# OrmerodController.net
KiCad netlist of a schematic drawn in EAGLE
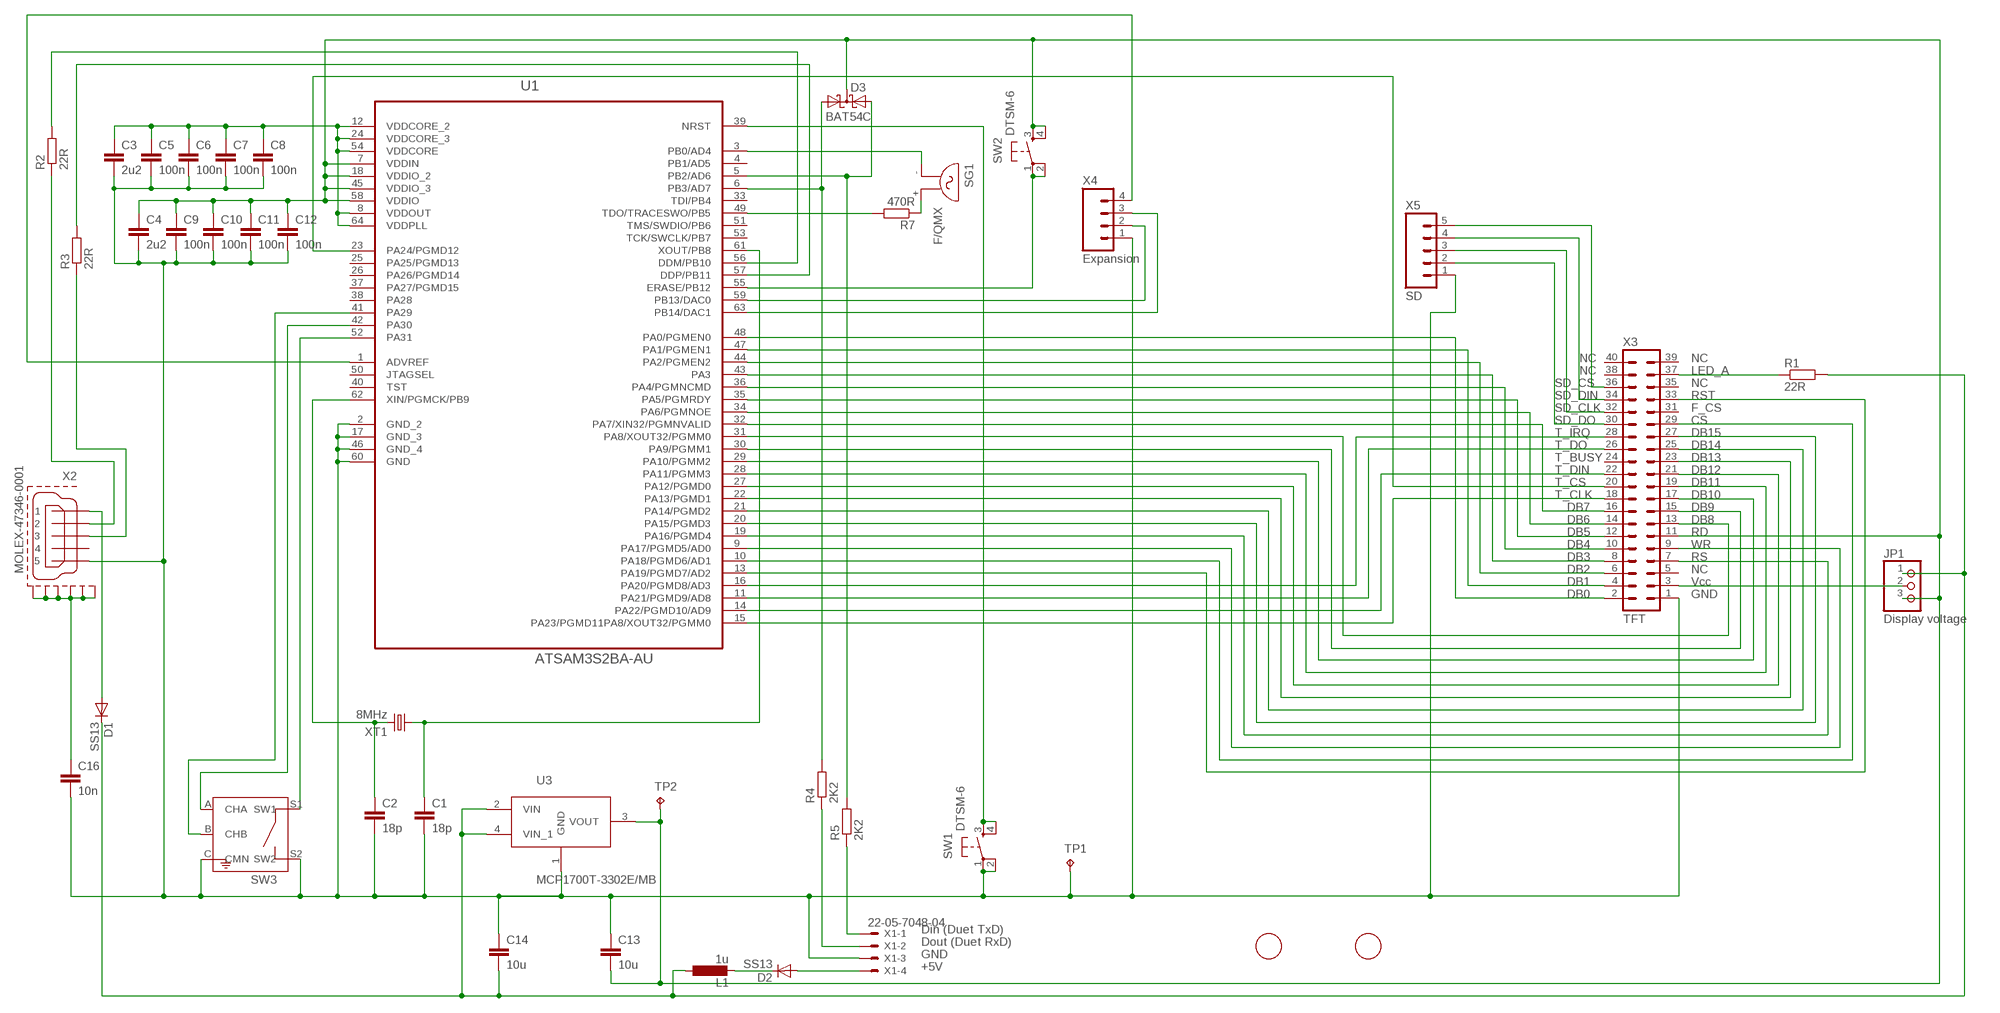
[diagram p0: schematic, sheet 1]

(export (version "E")
  (design (tool "Eeschema 10.0.6"))
  (components
    (comp (ref "C1")
      (value "18p")
      (footprint "eagle-import:C0603")
      (libsource (lib "eagle-import") (part "C-EUC0603"))
    )
    (comp (ref "C2")
      (value "18p")
      (footprint "eagle-import:C0603")
      (libsource (lib "eagle-import") (part "C-EUC0603"))
    )
    (comp (ref "C3")
      (value "2u2")
      (footprint "eagle-import:C0603")
      (libsource (lib "eagle-import") (part "C-EUC0603"))
    )
    (comp (ref "C4")
      (value "2u2")
      (footprint "eagle-import:C0603")
      (libsource (lib "eagle-import") (part "C-EUC0603"))
    )
    (comp (ref "C5")
      (value "100n")
      (footprint "eagle-import:C0603")
      (libsource (lib "eagle-import") (part "C-EUC0603"))
    )
    (comp (ref "C6")
      (value "100n")
      (footprint "eagle-import:C0603")
      (libsource (lib "eagle-import") (part "C-EUC0603"))
    )
    (comp (ref "C7")
      (value "100n")
      (footprint "eagle-import:C0603")
      (libsource (lib "eagle-import") (part "C-EUC0603"))
    )
    (comp (ref "C8")
      (value "100n")
      (footprint "eagle-import:C0603")
      (libsource (lib "eagle-import") (part "C-EUC0603"))
    )
    (comp (ref "C9")
      (value "100n")
      (footprint "eagle-import:C0603")
      (libsource (lib "eagle-import") (part "C-EUC0603"))
    )
    (comp (ref "C10")
      (value "100n")
      (footprint "eagle-import:C0603")
      (libsource (lib "eagle-import") (part "C-EUC0603"))
    )
    (comp (ref "C11")
      (value "100n")
      (footprint "eagle-import:C0603")
      (libsource (lib "eagle-import") (part "C-EUC0603"))
    )
    (comp (ref "C12")
      (value "100n")
      (footprint "eagle-import:C0603")
      (libsource (lib "eagle-import") (part "C-EUC0603"))
    )
    (comp (ref "C13")
      (value "10u")
      (footprint "eagle-import:C0805")
      (libsource (lib "eagle-import") (part "C-EUC0805"))
    )
    (comp (ref "C14")
      (value "10u")
      (footprint "eagle-import:C0805")
      (libsource (lib "eagle-import") (part "C-EUC0805"))
    )
    (comp (ref "C16")
      (value "10n")
      (footprint "eagle-import:C0603")
      (libsource (lib "eagle-import") (part "C-EUC0603"))
    )
    (comp (ref "D1")
      (value "SS13")
      (footprint "eagle-import:DO214AC")
      (libsource (lib "eagle-import") (part "DIODE-DO214AC"))
    )
    (comp (ref "D2")
      (value "SS13")
      (footprint "eagle-import:DO214AC")
      (libsource (lib "eagle-import") (part "DIODE-DO214AC"))
    )
    (comp (ref "D3")
      (value "BAT54C")
      (footprint "eagle-import:SOT23")
      (libsource (lib "eagle-import") (part "BAT54C"))
    )
    (comp (ref "JP1")
      (value "Display voltage")
      (footprint "eagle-import:1X03")
      (libsource (lib "eagle-import") (part "PINHD-1X3"))
    )
    (comp (ref "L1")
      (value "1u")
      (footprint "eagle-import:L2012C")
      (libsource (lib "eagle-import") (part "L-EUL2012C"))
    )
    (comp (ref "R1")
      (value "22R")
      (footprint "eagle-import:R0805")
      (libsource (lib "eagle-import") (part "R-EU_R0805"))
    )
    (comp (ref "R2")
      (value "22R")
      (footprint "eagle-import:R0603")
      (libsource (lib "eagle-import") (part "R-EU_R0603"))
    )
    (comp (ref "R3")
      (value "22R")
      (footprint "eagle-import:R0603")
      (libsource (lib "eagle-import") (part "R-EU_R0603"))
    )
    (comp (ref "R4")
      (value "2K2")
      (footprint "eagle-import:R0603")
      (libsource (lib "eagle-import") (part "R-EU_R0603"))
    )
    (comp (ref "R5")
      (value "2K2")
      (footprint "eagle-import:R0603")
      (libsource (lib "eagle-import") (part "R-EU_R0603"))
    )
    (comp (ref "R7")
      (value "470R")
      (footprint "eagle-import:R0603")
      (libsource (lib "eagle-import") (part "R-EU_R0603"))
    )
    (comp (ref "SG1")
      (value "F/QMX")
      (footprint "eagle-import:F_QMX")
      (libsource (lib "eagle-import") (part "F/QMX"))
    )
    (comp (ref "SW1")
      (value "DTSM-6")
      (footprint "eagle-import:DTSM-6")
      (libsource (lib "eagle-import") (part "DTSM-6"))
    )
    (comp (ref "SW2")
      (value "DTSM-6")
      (footprint "eagle-import:DTSM-6")
      (libsource (lib "eagle-import") (part "DTSM-6"))
    )
    (comp (ref "SW3")
      (value "PEC12_ENCODER")
      (footprint "eagle-import:PEC12_ENCODER")
      (libsource (lib "eagle-import") (part "PEC12_ENCODER"))
    )
    (comp (ref "TP1")
      (value "TPPAD1-10")
      (footprint "eagle-import:P1-10")
      (libsource (lib "eagle-import") (part "TPPAD1-10"))
    )
    (comp (ref "TP2")
      (value "TPPAD1-10")
      (footprint "eagle-import:P1-10")
      (libsource (lib "eagle-import") (part "TPPAD1-10"))
    )
    (comp (ref "U$1")
      (value "FIDUCIAL")
      (footprint "eagle-import:FIDUCIAL_1MM")
      (libsource (lib "eagle-import") (part "FIDUCIAL"))
    )
    (comp (ref "U$2")
      (value "FIDUCIAL")
      (footprint "eagle-import:FIDUCIAL_1MM")
      (libsource (lib "eagle-import") (part "FIDUCIAL"))
    )
    (comp (ref "U1")
      (value "ATSAM3S2BA-AU")
      (footprint "eagle-import:QFP50P1200X1200X160-64N")
      (libsource (lib "eagle-import") (part "ATSAM3S2BA-AU"))
    )
    (comp (ref "U3")
      (value "MCP1700T-3302E/MB")
      (footprint "eagle-import:SOT150P400X160-4N")
      (fields (field (name "MPN") "MCP1702T-3302E/MB"))
      (libsource (lib "eagle-import") (part "MCP17-MCP1702T-3302E/MB"))
    )
    (comp (ref "X1")
      (value "22-05-7048-04")
      (footprint "eagle-import:7395-04")
      (libsource (lib "eagle-import") (part "22-?-0405-7048"))
    )
    (comp (ref "X2")
      (value "MOLEX-47346-0001")
      (footprint "eagle-import:MOLEX-47364-0001")
      (libsource (lib "eagle-import") (part "MOLEX-47346-0001"))
    )
    (comp (ref "X3")
      (value "TFT")
      (footprint "eagle-import:MA20-2")
      (libsource (lib "eagle-import") (part "MA20-2"))
    )
    (comp (ref "X4")
      (value "Expansion")
      (footprint "eagle-import:1X04")
      (libsource (lib "eagle-import") (part "M04PTH"))
    )
    (comp (ref "X5")
      (value "SD")
      (footprint "eagle-import:1X05")
      (libsource (lib "eagle-import") (part "M05PTH"))
    )
    (comp (ref "XT1")
      (value "8MHz")
      (footprint "eagle-import:HC49U-V")
      (libsource (lib "eagle-import") (part "CRYSTALHC49U-V"))
    )
  )
  (nets
    (net (code "1") (name "Net-(C16-Pad1)") (class "Default")
      (node (ref "C16") (pin "1") (pinfunction "1_1") (pintype "passive"))
      (node (ref "X2") (pin "GND1") (pinfunction "GND1_GND1") (pintype "bidirectional"))
      (node (ref "X2") (pin "GND2") (pinfunction "GND2_GND2") (pintype "bidirectional"))
      (node (ref "X2") (pin "GND3") (pinfunction "GND3_GND3") (pintype "bidirectional"))
      (node (ref "X2") (pin "GND4") (pinfunction "GND4_GND4") (pintype "bidirectional"))
      (node (ref "X2") (pin "GND5") (pinfunction "GND5_GND5") (pintype "bidirectional"))
      (node (ref "X2") (pin "GND6") (pinfunction "GND6_GND6") (pintype "bidirectional"))
    )
    (net (code "2") (name "Net-(D1-PadA)") (class "Default")
      (node (ref "D1") (pin "A") (pinfunction "A_A") (pintype "passive"))
      (node (ref "X2") (pin "1") (pinfunction "1_1") (pintype "input"))
    )
    (net (code "3") (name "Net-(D2-PadC)") (class "Default")
      (node (ref "D2") (pin "C") (pinfunction "C_C") (pintype "passive"))
      (node (ref "L1") (pin "2") (pinfunction "2_2") (pintype "passive"))
    )
    (net (code "4") (name "Net-(D3-A1)") (class "Default")
      (node (ref "D3") (pin "1") (pinfunction "A1_1") (pintype "passive"))
      (node (ref "R4") (pin "2") (pinfunction "2_2") (pintype "passive"))
      (node (ref "U1") (pin "6") (pinfunction "PB3/AD7_6") (pintype "bidirectional"))
    )
    (net (code "5") (name "Net-(D3-A2)") (class "Default")
      (node (ref "D3") (pin "2") (pinfunction "A2_2") (pintype "passive"))
      (node (ref "R5") (pin "2") (pinfunction "2_2") (pintype "passive"))
      (node (ref "U1") (pin "5") (pinfunction "PB2/AD6_5") (pintype "bidirectional"))
    )
    (net (code "6") (name "Net-(D3-CC)") (class "Default")
      (node (ref "C10") (pin "1") (pinfunction "1_1") (pintype "passive"))
      (node (ref "C11") (pin "1") (pinfunction "1_1") (pintype "passive"))
      (node (ref "C12") (pin "1") (pinfunction "1_1") (pintype "passive"))
      (node (ref "C13") (pin "2") (pinfunction "2_2") (pintype "passive"))
      (node (ref "C4") (pin "1") (pinfunction "1_1") (pintype "passive"))
      (node (ref "C9") (pin "1") (pinfunction "1_1") (pintype "passive"))
      (node (ref "D3") (pin "3") (pinfunction "CC_3") (pintype "passive"))
      (node (ref "JP1") (pin "3") (pinfunction "3_3") (pintype "passive"))
      (node (ref "SW2") (pin "3") (pinfunction "3_3") (pintype "passive"))
      (node (ref "SW2") (pin "4") (pinfunction "4_4") (pintype "passive"))
      (node (ref "TP2") (pin "TP") (pinfunction "TP_TP") (pintype "input"))
      (node (ref "U1") (pin "18") (pinfunction "VDDIO_2_18") (pintype "power_in"))
      (node (ref "U1") (pin "45") (pinfunction "VDDIO_3_45") (pintype "power_in"))
      (node (ref "U1") (pin "58") (pinfunction "VDDIO_58") (pintype "power_in"))
      (node (ref "U1") (pin "7") (pinfunction "VDDIN_7") (pintype "power_in"))
      (node (ref "U3") (pin "3") (pinfunction "VOUT_3") (pintype "output"))
      (node (ref "X3") (pin "11") (pinfunction "11_11") (pintype "passive"))
    )
    (net (code "7") (name "Net-(JP1-Pad2)") (class "Default")
      (node (ref "JP1") (pin "2") (pinfunction "2_2") (pintype "passive"))
      (node (ref "X3") (pin "3") (pinfunction "3_3") (pintype "passive"))
    )
    (net (code "8") (name "Net-(R1-Pad1)") (class "Default")
      (node (ref "R1") (pin "1") (pinfunction "1_1") (pintype "passive"))
      (node (ref "X3") (pin "37") (pinfunction "37_37") (pintype "passive"))
    )
    (net (code "9") (name "Net-(R2-Pad1)") (class "Default")
      (node (ref "R2") (pin "1") (pinfunction "1_1") (pintype "passive"))
      (node (ref "X2") (pin "2") (pinfunction "2_2") (pintype "input"))
    )
    (net (code "10") (name "Net-(R3-Pad1)") (class "Default")
      (node (ref "R3") (pin "1") (pinfunction "1_1") (pintype "passive"))
      (node (ref "X2") (pin "3") (pinfunction "3_3") (pintype "input"))
    )
    (net (code "11") (name "Net-(SG1-1)") (class "Default")
      (node (ref "SG1") (pin "-") (pinfunction "1_-") (pintype "passive"))
      (node (ref "U1") (pin "3") (pinfunction "PB0/AD4_3") (pintype "bidirectional"))
    )
    (net (code "12") (name "Net-(SG1-2)") (class "Default")
      (node (ref "R7") (pin "1") (pinfunction "1_1") (pintype "passive"))
      (node (ref "SG1") (pin "+") (pinfunction "2_+") (pintype "passive"))
    )
    (net (code "13") (name "Net-(SW3-CHA)") (class "Default")
      (node (ref "SW3") (pin "A") (pinfunction "CHA_A") (pintype "bidirectional"))
      (node (ref "U1") (pin "42") (pinfunction "PA30_42") (pintype "bidirectional"))
    )
    (net (code "14") (name "Net-(SW3-CHB)") (class "Default")
      (node (ref "SW3") (pin "B") (pinfunction "CHB_B") (pintype "bidirectional"))
      (node (ref "U1") (pin "41") (pinfunction "PA29_41") (pintype "bidirectional"))
    )
    (net (code "15") (name "Net-(SW3-CMN)") (class "Default")
      (node (ref "C1") (pin "2") (pinfunction "2_2") (pintype "passive"))
      (node (ref "C10") (pin "2") (pinfunction "2_2") (pintype "passive"))
      (node (ref "C11") (pin "2") (pinfunction "2_2") (pintype "passive"))
      (node (ref "C12") (pin "2") (pinfunction "2_2") (pintype "passive"))
      (node (ref "C13") (pin "1") (pinfunction "1_1") (pintype "passive"))
      (node (ref "C14") (pin "1") (pinfunction "1_1") (pintype "passive"))
      (node (ref "C16") (pin "2") (pinfunction "2_2") (pintype "passive"))
      (node (ref "C2") (pin "2") (pinfunction "2_2") (pintype "passive"))
      (node (ref "C3") (pin "2") (pinfunction "2_2") (pintype "passive"))
      (node (ref "C4") (pin "2") (pinfunction "2_2") (pintype "passive"))
      (node (ref "C5") (pin "2") (pinfunction "2_2") (pintype "passive"))
      (node (ref "C6") (pin "2") (pinfunction "2_2") (pintype "passive"))
      (node (ref "C7") (pin "2") (pinfunction "2_2") (pintype "passive"))
      (node (ref "C8") (pin "2") (pinfunction "2_2") (pintype "passive"))
      (node (ref "C9") (pin "2") (pinfunction "2_2") (pintype "passive"))
      (node (ref "SW1") (pin "1") (pinfunction "1_1") (pintype "passive"))
      (node (ref "SW1") (pin "2") (pinfunction "2_2") (pintype "passive"))
      (node (ref "SW3") (pin "C") (pinfunction "CMN_C") (pintype "bidirectional"))
      (node (ref "SW3") (pin "S2") (pinfunction "SW2_S2") (pintype "bidirectional"))
      (node (ref "TP1") (pin "TP") (pinfunction "TP_TP") (pintype "input"))
      (node (ref "U1") (pin "17") (pinfunction "GND_3_17") (pintype "passive"))
      (node (ref "U1") (pin "2") (pinfunction "GND_2_2") (pintype "passive"))
      (node (ref "U1") (pin "46") (pinfunction "GND_4_46") (pintype "passive"))
      (node (ref "U1") (pin "60") (pinfunction "GND_60") (pintype "passive"))
      (node (ref "U3") (pin "1") (pinfunction "GND_1") (pintype "power_in"))
      (node (ref "X1") (pin "3") (pinfunction "S_3") (pintype "passive"))
      (node (ref "X2") (pin "5") (pinfunction "5_5") (pintype "input"))
      (node (ref "X3") (pin "1") (pinfunction "1_1") (pintype "passive"))
      (node (ref "X4") (pin "1") (pinfunction "1_1") (pintype "passive"))
      (node (ref "X5") (pin "1") (pinfunction "1_1") (pintype "passive"))
    )
    (net (code "16") (name "Net-(SW3-SW1)") (class "Default")
      (node (ref "SW3") (pin "S1") (pinfunction "SW1_S1") (pintype "bidirectional"))
      (node (ref "U1") (pin "52") (pinfunction "PA31_52") (pintype "bidirectional"))
    )
    (net (code "17") (name "Net-(U1-ADVREF)") (class "Default")
      (node (ref "U1") (pin "1") (pinfunction "ADVREF_1") (pintype "input"))
      (node (ref "X4") (pin "4") (pinfunction "4_4") (pintype "passive"))
    )
    (net (code "18") (name "Net-(U1-DDM{slash}PB10)") (class "Default")
      (node (ref "R2") (pin "2") (pinfunction "2_2") (pintype "passive"))
      (node (ref "U1") (pin "56") (pinfunction "DDM/PB10_56") (pintype "bidirectional"))
    )
    (net (code "19") (name "Net-(U1-DDP{slash}PB11)") (class "Default")
      (node (ref "R3") (pin "2") (pinfunction "2_2") (pintype "passive"))
      (node (ref "U1") (pin "57") (pinfunction "DDP/PB11_57") (pintype "bidirectional"))
    )
    (net (code "20") (name "Net-(U1-ERASE{slash}PB12)") (class "Default")
      (node (ref "SW2") (pin "1") (pinfunction "1_1") (pintype "passive"))
      (node (ref "SW2") (pin "2") (pinfunction "2_2") (pintype "passive"))
      (node (ref "U1") (pin "55") (pinfunction "ERASE/PB12_55") (pintype "bidirectional"))
    )
    (net (code "21") (name "Net-(U1-NRST)") (class "Default")
      (node (ref "SW1") (pin "3") (pinfunction "3_3") (pintype "passive"))
      (node (ref "SW1") (pin "4") (pinfunction "4_4") (pintype "passive"))
      (node (ref "U1") (pin "39") (pinfunction "NRST_39") (pintype "bidirectional"))
    )
    (net (code "22") (name "Net-(U1-PA0{slash}PGMEN0)") (class "Default")
      (node (ref "U1") (pin "48") (pinfunction "PA0/PGMEN0_48") (pintype "bidirectional"))
      (node (ref "X3") (pin "2") (pinfunction "2_2") (pintype "passive"))
    )
    (net (code "23") (name "Net-(U1-PA1{slash}PGMEN1)") (class "Default")
      (node (ref "U1") (pin "47") (pinfunction "PA1/PGMEN1_47") (pintype "bidirectional"))
      (node (ref "X3") (pin "4") (pinfunction "4_4") (pintype "passive"))
    )
    (net (code "24") (name "Net-(U1-PA2{slash}PGMEN2)") (class "Default")
      (node (ref "U1") (pin "44") (pinfunction "PA2/PGMEN2_44") (pintype "bidirectional"))
      (node (ref "X3") (pin "6") (pinfunction "6_6") (pintype "passive"))
    )
    (net (code "25") (name "Net-(U1-PA3)") (class "Default")
      (node (ref "U1") (pin "43") (pinfunction "PA3_43") (pintype "bidirectional"))
      (node (ref "X3") (pin "8") (pinfunction "8_8") (pintype "passive"))
    )
    (net (code "26") (name "Net-(U1-PA4{slash}PGMNCMD)") (class "Default")
      (node (ref "U1") (pin "36") (pinfunction "PA4/PGMNCMD_36") (pintype "bidirectional"))
      (node (ref "X3") (pin "10") (pinfunction "10_10") (pintype "passive"))
    )
    (net (code "27") (name "Net-(U1-PA5{slash}PGMRDY)") (class "Default")
      (node (ref "U1") (pin "35") (pinfunction "PA5/PGMRDY_35") (pintype "bidirectional"))
      (node (ref "X3") (pin "12") (pinfunction "12_12") (pintype "passive"))
    )
    (net (code "28") (name "Net-(U1-PA6{slash}PGMNOE)") (class "Default")
      (node (ref "U1") (pin "34") (pinfunction "PA6/PGMNOE_34") (pintype "bidirectional"))
      (node (ref "X3") (pin "14") (pinfunction "14_14") (pintype "passive"))
    )
    (net (code "29") (name "Net-(U1-PA7{slash}XIN32{slash}PGMNVALID)") (class "Default")
      (node (ref "U1") (pin "32") (pinfunction "PA7/XIN32/PGMNVALID_32") (pintype "bidirectional"))
      (node (ref "X3") (pin "16") (pinfunction "16_16") (pintype "passive"))
    )
    (net (code "30") (name "Net-(U1-PA8{slash}XOUT32{slash}PGMM0)") (class "Default")
      (node (ref "U1") (pin "31") (pinfunction "PA8/XOUT32/PGMM0_31") (pintype "bidirectional"))
      (node (ref "X3") (pin "13") (pinfunction "13_13") (pintype "passive"))
    )
    (net (code "31") (name "Net-(U1-PA9{slash}PGMM1)") (class "Default")
      (node (ref "U1") (pin "30") (pinfunction "PA9/PGMM1_30") (pintype "bidirectional"))
      (node (ref "X3") (pin "15") (pinfunction "15_15") (pintype "passive"))
    )
    (net (code "32") (name "Net-(U1-PA10{slash}PGMM2)") (class "Default")
      (node (ref "U1") (pin "29") (pinfunction "PA10/PGMM2_29") (pintype "bidirectional"))
      (node (ref "X3") (pin "17") (pinfunction "17_17") (pintype "passive"))
    )
    (net (code "33") (name "Net-(U1-PA11{slash}PGMM3)") (class "Default")
      (node (ref "U1") (pin "28") (pinfunction "PA11/PGMM3_28") (pintype "bidirectional"))
      (node (ref "X3") (pin "19") (pinfunction "19_19") (pintype "passive"))
    )
    (net (code "34") (name "Net-(U1-PA12{slash}PGMD0)") (class "Default")
      (node (ref "U1") (pin "27") (pinfunction "PA12/PGMD0_27") (pintype "bidirectional"))
      (node (ref "X3") (pin "21") (pinfunction "21_21") (pintype "passive"))
    )
    (net (code "35") (name "Net-(U1-PA13{slash}PGMD1)") (class "Default")
      (node (ref "U1") (pin "22") (pinfunction "PA13/PGMD1_22") (pintype "bidirectional"))
      (node (ref "X3") (pin "23") (pinfunction "23_23") (pintype "passive"))
    )
    (net (code "36") (name "Net-(U1-PA14{slash}PGMD2)") (class "Default")
      (node (ref "U1") (pin "21") (pinfunction "PA14/PGMD2_21") (pintype "bidirectional"))
      (node (ref "X3") (pin "25") (pinfunction "25_25") (pintype "passive"))
    )
    (net (code "37") (name "Net-(U1-PA15{slash}PGMD3)") (class "Default")
      (node (ref "U1") (pin "20") (pinfunction "PA15/PGMD3_20") (pintype "bidirectional"))
      (node (ref "X3") (pin "27") (pinfunction "27_27") (pintype "passive"))
    )
    (net (code "38") (name "Net-(U1-PA16{slash}PGMD4)") (class "Default")
      (node (ref "U1") (pin "19") (pinfunction "PA16/PGMD4_19") (pintype "bidirectional"))
      (node (ref "X3") (pin "7") (pinfunction "7_7") (pintype "passive"))
    )
    (net (code "39") (name "Net-(U1-PA17{slash}PGMD5{slash}AD0)") (class "Default")
      (node (ref "U1") (pin "9") (pinfunction "PA17/PGMD5/AD0_9") (pintype "bidirectional"))
      (node (ref "X3") (pin "9") (pinfunction "9_9") (pintype "passive"))
    )
    (net (code "40") (name "Net-(U1-PA18{slash}PGMD6{slash}AD1)") (class "Default")
      (node (ref "U1") (pin "10") (pinfunction "PA18/PGMD6/AD1_10") (pintype "bidirectional"))
      (node (ref "X3") (pin "29") (pinfunction "29_29") (pintype "passive"))
    )
    (net (code "41") (name "Net-(U1-PA19{slash}PGMD7{slash}AD2)") (class "Default")
      (node (ref "U1") (pin "13") (pinfunction "PA19/PGMD7/AD2_13") (pintype "bidirectional"))
      (node (ref "X3") (pin "33") (pinfunction "33_33") (pintype "passive"))
    )
    (net (code "42") (name "Net-(U1-PA20{slash}PGMD8{slash}AD3)") (class "Default")
      (node (ref "U1") (pin "16") (pinfunction "PA20/PGMD8/AD3_16") (pintype "bidirectional"))
      (node (ref "X3") (pin "28") (pinfunction "28_28") (pintype "passive"))
    )
    (net (code "43") (name "Net-(U1-PA21{slash}PGMD9{slash}AD8)") (class "Default")
      (node (ref "U1") (pin "11") (pinfunction "PA21/PGMD9/AD8_11") (pintype "bidirectional"))
      (node (ref "X3") (pin "26") (pinfunction "26_26") (pintype "passive"))
    )
    (net (code "44") (name "Net-(U1-PA22{slash}PGMD10{slash}AD9)") (class "Default")
      (node (ref "U1") (pin "14") (pinfunction "PA22/PGMD10/AD9_14") (pintype "bidirectional"))
      (node (ref "X3") (pin "22") (pinfunction "22_22") (pintype "passive"))
    )
    (net (code "45") (name "Net-(U1-PA23{slash}PGMD11PA8{slash}XOUT32{slash}PGMM0)") (class "Default")
      (node (ref "U1") (pin "15") (pinfunction "PA23/PGMD11PA8/XOUT32/PGMM0_15") (pintype "bidirectional"))
      (node (ref "X3") (pin "18") (pinfunction "18_18") (pintype "passive"))
    )
    (net (code "46") (name "Net-(U1-PA24{slash}PGMD12)") (class "Default")
      (node (ref "U1") (pin "23") (pinfunction "PA24/PGMD12_23") (pintype "bidirectional"))
      (node (ref "X3") (pin "20") (pinfunction "20_20") (pintype "passive"))
    )
    (net (code "47") (name "Net-(U1-PB13{slash}DAC0)") (class "Default")
      (node (ref "U1") (pin "59") (pinfunction "PB13/DAC0_59") (pintype "bidirectional"))
      (node (ref "X4") (pin "2") (pinfunction "2_2") (pintype "passive"))
    )
    (net (code "48") (name "Net-(U1-PB14{slash}DAC1)") (class "Default")
      (node (ref "U1") (pin "63") (pinfunction "PB14/DAC1_63") (pintype "bidirectional"))
      (node (ref "X4") (pin "3") (pinfunction "3_3") (pintype "passive"))
    )
    (net (code "49") (name "Net-(U1-TDO{slash}TRACESWO{slash}PB5)") (class "Default")
      (node (ref "R7") (pin "2") (pinfunction "2_2") (pintype "passive"))
      (node (ref "U1") (pin "49") (pinfunction "TDO/TRACESWO/PB5_49") (pintype "bidirectional"))
    )
    (net (code "50") (name "Net-(U1-VDDCORE)") (class "Default")
      (node (ref "C3") (pin "1") (pinfunction "1_1") (pintype "passive"))
      (node (ref "C5") (pin "1") (pinfunction "1_1") (pintype "passive"))
      (node (ref "C6") (pin "1") (pinfunction "1_1") (pintype "passive"))
      (node (ref "C7") (pin "1") (pinfunction "1_1") (pintype "passive"))
      (node (ref "C8") (pin "1") (pinfunction "1_1") (pintype "passive"))
      (node (ref "U1") (pin "12") (pinfunction "VDDCORE_2_12") (pintype "power_in"))
      (node (ref "U1") (pin "24") (pinfunction "VDDCORE_3_24") (pintype "power_in"))
      (node (ref "U1") (pin "54") (pinfunction "VDDCORE_54") (pintype "power_in"))
      (node (ref "U1") (pin "64") (pinfunction "VDDPLL_64") (pintype "power_in"))
      (node (ref "U1") (pin "8") (pinfunction "VDDOUT_8") (pintype "power_in"))
    )
    (net (code "51") (name "Net-(U1-XIN{slash}PGMCK{slash}PB9)") (class "Default")
      (node (ref "C2") (pin "1") (pinfunction "1_1") (pintype "passive"))
      (node (ref "U1") (pin "62") (pinfunction "XIN/PGMCK/PB9_62") (pintype "input"))
      (node (ref "XT1") (pin "2") (pinfunction "2_2") (pintype "passive"))
    )
    (net (code "52") (name "Net-(U1-XOUT{slash}PB8)") (class "Default")
      (node (ref "C1") (pin "1") (pinfunction "1_1") (pintype "passive"))
      (node (ref "U1") (pin "61") (pinfunction "XOUT/PB8_61") (pintype "output"))
      (node (ref "XT1") (pin "1") (pinfunction "1_1") (pintype "passive"))
    )
    (net (code "53") (name "Net-(U3-VIN)") (class "Default")
      (node (ref "C14") (pin "2") (pinfunction "2_2") (pintype "passive"))
      (node (ref "D1") (pin "C") (pinfunction "C_C") (pintype "passive"))
      (node (ref "JP1") (pin "1") (pinfunction "1_1") (pintype "passive"))
      (node (ref "L1") (pin "1") (pinfunction "1_1") (pintype "passive"))
      (node (ref "R1") (pin "2") (pinfunction "2_2") (pintype "passive"))
      (node (ref "U3") (pin "2") (pinfunction "VIN_2") (pintype "input"))
      (node (ref "U3") (pin "4") (pinfunction "VIN_1_4") (pintype "input"))
    )
    (net (code "54") (name "Net-(X1A-S)") (class "Default")
      (node (ref "R5") (pin "1") (pinfunction "1_1") (pintype "passive"))
      (node (ref "X1") (pin "1") (pinfunction "S_1") (pintype "passive"))
    )
    (net (code "55") (name "Net-(X1B-S)") (class "Default")
      (node (ref "R4") (pin "1") (pinfunction "1_1") (pintype "passive"))
      (node (ref "X1") (pin "2") (pinfunction "S_2") (pintype "passive"))
    )
    (net (code "56") (name "Net-(X1D-S)") (class "Default")
      (node (ref "D2") (pin "A") (pinfunction "A_A") (pintype "passive"))
      (node (ref "X1") (pin "4") (pinfunction "S_4") (pintype "passive"))
    )
    (net (code "57") (name "Net-(X3-Pad30)") (class "Default")
      (node (ref "X3") (pin "30") (pinfunction "30_30") (pintype "passive"))
      (node (ref "X5") (pin "2") (pinfunction "2_2") (pintype "passive"))
    )
    (net (code "58") (name "Net-(X3-Pad32)") (class "Default")
      (node (ref "X3") (pin "32") (pinfunction "32_32") (pintype "passive"))
      (node (ref "X5") (pin "3") (pinfunction "3_3") (pintype "passive"))
    )
    (net (code "59") (name "Net-(X3-Pad34)") (class "Default")
      (node (ref "X3") (pin "34") (pinfunction "34_34") (pintype "passive"))
      (node (ref "X5") (pin "4") (pinfunction "4_4") (pintype "passive"))
    )
    (net (code "60") (name "Net-(X3-Pad36)") (class "Default")
      (node (ref "X3") (pin "36") (pinfunction "36_36") (pintype "passive"))
      (node (ref "X5") (pin "5") (pinfunction "5_5") (pintype "passive"))
    )
    (net (code "61") (name "unconnected-(U1-JTAGSEL-Pad50)") (class "Default")
      (node (ref "U1") (pin "50") (pinfunction "JTAGSEL_50") (pintype "input"))
    )
    (net (code "62") (name "unconnected-(U1-PA25{slash}PGMD13-Pad25)") (class "Default")
      (node (ref "U1") (pin "25") (pinfunction "PA25/PGMD13_25") (pintype "bidirectional"))
    )
    (net (code "63") (name "unconnected-(U1-PA26{slash}PGMD14-Pad26)") (class "Default")
      (node (ref "U1") (pin "26") (pinfunction "PA26/PGMD14_26") (pintype "bidirectional"))
    )
    (net (code "64") (name "unconnected-(U1-PA27{slash}PGMD15-Pad37)") (class "Default")
      (node (ref "U1") (pin "37") (pinfunction "PA27/PGMD15_37") (pintype "bidirectional"))
    )
    (net (code "65") (name "unconnected-(U1-PA28-Pad38)") (class "Default")
      (node (ref "U1") (pin "38") (pinfunction "PA28_38") (pintype "bidirectional"))
    )
    (net (code "66") (name "unconnected-(U1-PB1{slash}AD5-Pad4)") (class "Default")
      (node (ref "U1") (pin "4") (pinfunction "PB1/AD5_4") (pintype "bidirectional"))
    )
    (net (code "67") (name "unconnected-(U1-TCK{slash}SWCLK{slash}PB7-Pad53)") (class "Default")
      (node (ref "U1") (pin "53") (pinfunction "TCK/SWCLK/PB7_53") (pintype "bidirectional"))
    )
    (net (code "68") (name "unconnected-(U1-TDI{slash}PB4-Pad33)") (class "Default")
      (node (ref "U1") (pin "33") (pinfunction "TDI/PB4_33") (pintype "bidirectional"))
    )
    (net (code "69") (name "unconnected-(U1-TMS{slash}SWDIO{slash}PB6-Pad51)") (class "Default")
      (node (ref "U1") (pin "51") (pinfunction "TMS/SWDIO/PB6_51") (pintype "bidirectional"))
    )
    (net (code "70") (name "unconnected-(U1-TST-Pad40)") (class "Default")
      (node (ref "U1") (pin "40") (pinfunction "TST_40") (pintype "input"))
    )
    (net (code "71") (name "unconnected-(X2-Pad4)") (class "Default")
      (node (ref "X2") (pin "4") (pinfunction "4_4") (pintype "input"))
    )
    (net (code "72") (name "unconnected-(X3-Pad5)") (class "Default")
      (node (ref "X3") (pin "5") (pinfunction "5_5") (pintype "passive"))
    )
    (net (code "73") (name "unconnected-(X3-Pad24)") (class "Default")
      (node (ref "X3") (pin "24") (pinfunction "24_24") (pintype "passive"))
    )
    (net (code "74") (name "unconnected-(X3-Pad31)") (class "Default")
      (node (ref "X3") (pin "31") (pinfunction "31_31") (pintype "passive"))
    )
    (net (code "75") (name "unconnected-(X3-Pad35)") (class "Default")
      (node (ref "X3") (pin "35") (pinfunction "35_35") (pintype "passive"))
    )
    (net (code "76") (name "unconnected-(X3-Pad38)") (class "Default")
      (node (ref "X3") (pin "38") (pinfunction "38_38") (pintype "passive"))
    )
    (net (code "77") (name "unconnected-(X3-Pad39)") (class "Default")
      (node (ref "X3") (pin "39") (pinfunction "39_39") (pintype "passive"))
    )
    (net (code "78") (name "unconnected-(X3-Pad40)") (class "Default")
      (node (ref "X3") (pin "40") (pinfunction "40_40") (pintype "passive"))
    )
  )
)
